# main.net
KiCad netlist of a schematic drawn in EAGLE
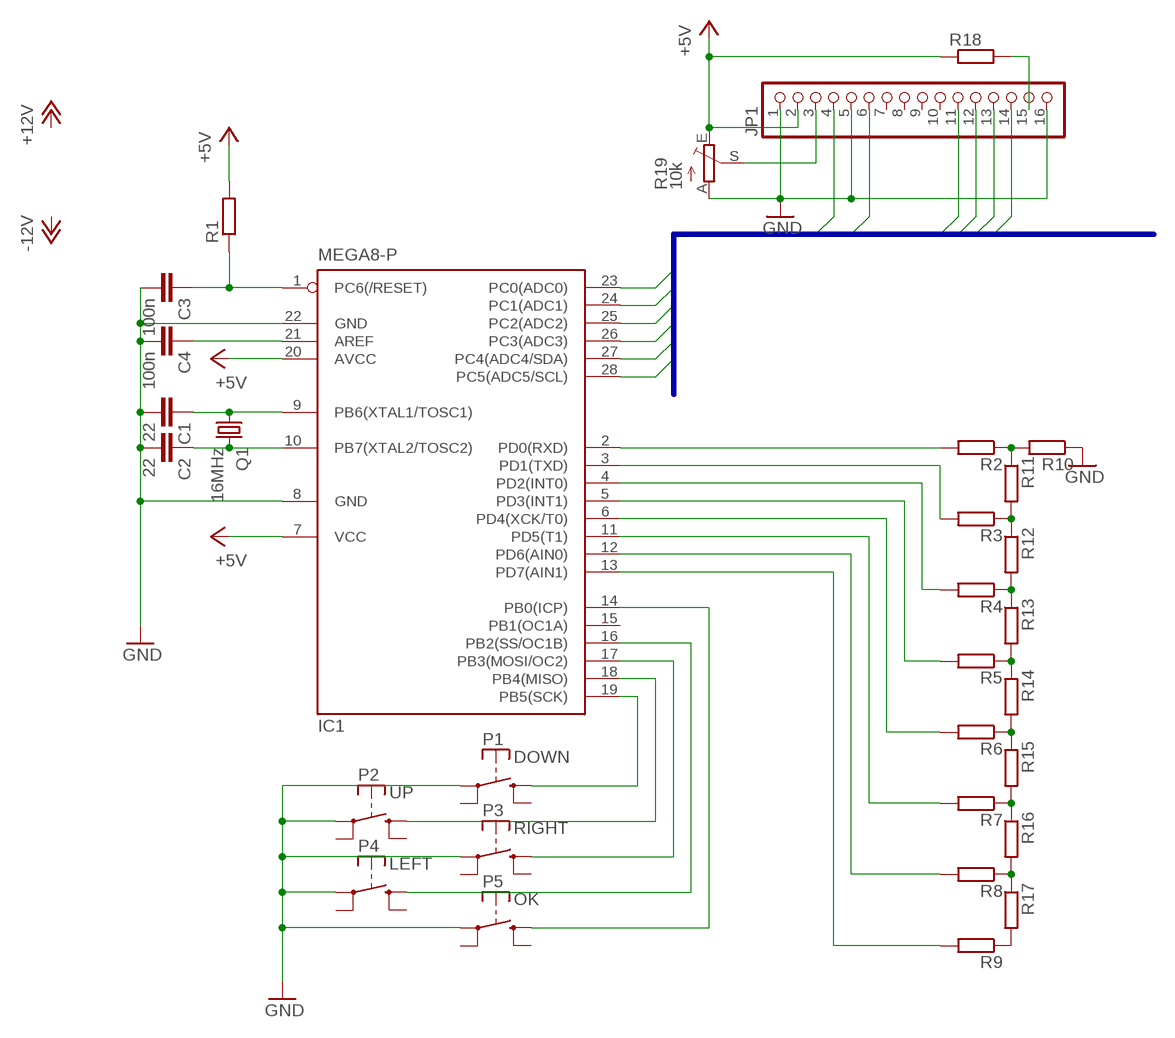
[diagram p0: schematic, sheet 1]

(export (version "E")
  (design (tool "Eeschema 10.0.6"))
  (components
    (comp (ref "C1")
      (value "22")
      (footprint "eagle-import:C0805")
      (libsource (lib "eagle-import") (part "C-EUC0805"))
    )
    (comp (ref "C2")
      (value "22")
      (footprint "eagle-import:C0805")
      (libsource (lib "eagle-import") (part "C-EUC0805"))
    )
    (comp (ref "C3")
      (value "100n")
      (footprint "eagle-import:C0805")
      (libsource (lib "eagle-import") (part "C-EUC0805"))
    )
    (comp (ref "C4")
      (value "100n")
      (footprint "eagle-import:C0805")
      (libsource (lib "eagle-import") (part "C-EUC0805"))
    )
    (comp (ref "IC1")
      (value "MEGA8-P")
      (footprint "eagle-import:DIL28-3")
      (libsource (lib "eagle-import") (part "MEGA8-P"))
    )
    (comp (ref "JP1")
      (value "PINHD-1X16")
      (footprint "eagle-import:1X16")
      (libsource (lib "eagle-import") (part "PINHD-1X16"))
    )
    (comp (ref "P1")
      (value "DOWN")
      (footprint "eagle-import:FSMCD")
      (libsource (lib "eagle-import") (part "FSMCD"))
    )
    (comp (ref "P2")
      (value "UP")
      (footprint "eagle-import:FSMCD")
      (libsource (lib "eagle-import") (part "FSMCD"))
    )
    (comp (ref "P3")
      (value "RIGHT")
      (footprint "eagle-import:FSMCD")
      (libsource (lib "eagle-import") (part "FSMCD"))
    )
    (comp (ref "P4")
      (value "LEFT")
      (footprint "eagle-import:FSMCD")
      (libsource (lib "eagle-import") (part "FSMCD"))
    )
    (comp (ref "P5")
      (value "OK")
      (footprint "eagle-import:FSMCD")
      (libsource (lib "eagle-import") (part "FSMCD"))
    )
    (comp (ref "Q1")
      (value "16MHz")
      (footprint "eagle-import:HC49_S")
      (libsource (lib "eagle-import") (part "CRYSTALHC49S"))
    )
    (comp (ref "R1")
      (value "R-EU_0207/10")
      (footprint "eagle-import:0207_10")
      (libsource (lib "eagle-import") (part "R-EU_0207/10"))
    )
    (comp (ref "R2")
      (value "R-EU_0207/10")
      (footprint "eagle-import:0207_10")
      (libsource (lib "eagle-import") (part "R-EU_0207/10"))
    )
    (comp (ref "R3")
      (value "R-EU_0207/10")
      (footprint "eagle-import:0207_10")
      (libsource (lib "eagle-import") (part "R-EU_0207/10"))
    )
    (comp (ref "R4")
      (value "R-EU_0207/10")
      (footprint "eagle-import:0207_10")
      (libsource (lib "eagle-import") (part "R-EU_0207/10"))
    )
    (comp (ref "R5")
      (value "R-EU_0207/10")
      (footprint "eagle-import:0207_10")
      (libsource (lib "eagle-import") (part "R-EU_0207/10"))
    )
    (comp (ref "R6")
      (value "R-EU_0207/10")
      (footprint "eagle-import:0207_10")
      (libsource (lib "eagle-import") (part "R-EU_0207/10"))
    )
    (comp (ref "R7")
      (value "R-EU_0207/10")
      (footprint "eagle-import:0207_10")
      (libsource (lib "eagle-import") (part "R-EU_0207/10"))
    )
    (comp (ref "R8")
      (value "R-EU_0207/10")
      (footprint "eagle-import:0207_10")
      (libsource (lib "eagle-import") (part "R-EU_0207/10"))
    )
    (comp (ref "R9")
      (value "R-EU_0207/10")
      (footprint "eagle-import:0207_10")
      (libsource (lib "eagle-import") (part "R-EU_0207/10"))
    )
    (comp (ref "R10")
      (value "R-EU_0207/10")
      (footprint "eagle-import:0207_10")
      (libsource (lib "eagle-import") (part "R-EU_0207/10"))
    )
    (comp (ref "R11")
      (value "R-EU_0207/10")
      (footprint "eagle-import:0207_10")
      (libsource (lib "eagle-import") (part "R-EU_0207/10"))
    )
    (comp (ref "R12")
      (value "R-EU_0207/10")
      (footprint "eagle-import:0207_10")
      (libsource (lib "eagle-import") (part "R-EU_0207/10"))
    )
    (comp (ref "R13")
      (value "R-EU_0207/10")
      (footprint "eagle-import:0207_10")
      (libsource (lib "eagle-import") (part "R-EU_0207/10"))
    )
    (comp (ref "R14")
      (value "R-EU_0207/10")
      (footprint "eagle-import:0207_10")
      (libsource (lib "eagle-import") (part "R-EU_0207/10"))
    )
    (comp (ref "R15")
      (value "R-EU_0207/10")
      (footprint "eagle-import:0207_10")
      (libsource (lib "eagle-import") (part "R-EU_0207/10"))
    )
    (comp (ref "R16")
      (value "R-EU_0207/10")
      (footprint "eagle-import:0207_10")
      (libsource (lib "eagle-import") (part "R-EU_0207/10"))
    )
    (comp (ref "R17")
      (value "R-EU_0207/10")
      (footprint "eagle-import:0207_10")
      (libsource (lib "eagle-import") (part "R-EU_0207/10"))
    )
    (comp (ref "R18")
      (value "R-EU_0207/10")
      (footprint "eagle-import:0207_10")
      (libsource (lib "eagle-import") (part "R-EU_0207/10"))
    )
    (comp (ref "R19")
      (value "10k")
      (footprint "eagle-import:CA6V")
      (libsource (lib "eagle-import") (part "TRIM_EU-CA6V"))
    )
  )
  (nets
    (net (code "1") (name "+5V") (class "Default")
      (node (ref "IC1") (pin "20") (pinfunction "AVCC_20") (pintype "power_in"))
      (node (ref "IC1") (pin "7") (pinfunction "VCC_7") (pintype "power_in"))
      (node (ref "JP1") (pin "2") (pinfunction "2_2") (pintype "passive"))
      (node (ref "R1") (pin "2") (pinfunction "2_2") (pintype "passive"))
      (node (ref "R18") (pin "1") (pinfunction "1_1") (pintype "passive"))
      (node (ref "R19") (pin "E") (pinfunction "E_E") (pintype "passive"))
    )
    (net (code "4") (name "/LCD_D4") (class "Default")
      (node (ref "IC1") (pin "23") (pinfunction "PC0(ADC0)_23") (pintype "bidirectional"))
      (node (ref "JP1") (pin "11") (pinfunction "11_11") (pintype "passive"))
    )
    (net (code "5") (name "/LCD_D5") (class "Default")
      (node (ref "IC1") (pin "24") (pinfunction "PC1(ADC1)_24") (pintype "bidirectional"))
      (node (ref "JP1") (pin "12") (pinfunction "12_12") (pintype "passive"))
    )
    (net (code "6") (name "/LCD_D6") (class "Default")
      (node (ref "IC1") (pin "25") (pinfunction "PC2(ADC2)_25") (pintype "bidirectional"))
      (node (ref "JP1") (pin "13") (pinfunction "13_13") (pintype "passive"))
    )
    (net (code "7") (name "/LCD_D7") (class "Default")
      (node (ref "IC1") (pin "26") (pinfunction "PC3(ADC3)_26") (pintype "bidirectional"))
      (node (ref "JP1") (pin "14") (pinfunction "14_14") (pintype "passive"))
    )
    (net (code "8") (name "/LCD_E") (class "Default")
      (node (ref "IC1") (pin "28") (pinfunction "PC5(ADC5/SCL)_28") (pintype "bidirectional"))
      (node (ref "JP1") (pin "6") (pinfunction "6_6") (pintype "passive"))
    )
    (net (code "9") (name "/LCD_RS") (class "Default")
      (node (ref "IC1") (pin "27") (pinfunction "PC4(ADC4/SDA)_27") (pintype "bidirectional"))
      (node (ref "JP1") (pin "4") (pinfunction "4_4") (pintype "passive"))
    )
    (net (code "10") (name "GND") (class "Default")
      (node (ref "C1") (pin "2") (pinfunction "2_2") (pintype "passive"))
      (node (ref "C2") (pin "2") (pinfunction "2_2") (pintype "passive"))
      (node (ref "C3") (pin "2") (pinfunction "2_2") (pintype "passive"))
      (node (ref "C4") (pin "2") (pinfunction "2_2") (pintype "passive"))
      (node (ref "IC1") (pin "22") (pinfunction "GND_22") (pintype "power_in"))
      (node (ref "IC1") (pin "8") (pinfunction "GND_8") (pintype "power_in"))
      (node (ref "JP1") (pin "1") (pinfunction "1_1") (pintype "passive"))
      (node (ref "JP1") (pin "16") (pinfunction "16_16") (pintype "passive"))
      (node (ref "JP1") (pin "5") (pinfunction "5_5") (pintype "passive"))
      (node (ref "P1") (pin "P$1") (pinfunction "P_P$1") (pintype "passive"))
      (node (ref "P2") (pin "P$1") (pinfunction "P_P$1") (pintype "passive"))
      (node (ref "P3") (pin "P$1") (pinfunction "P_P$1") (pintype "passive"))
      (node (ref "P4") (pin "P$1") (pinfunction "P_P$1") (pintype "passive"))
      (node (ref "P5") (pin "P$1") (pinfunction "P_P$1") (pintype "passive"))
      (node (ref "R10") (pin "1") (pinfunction "1_1") (pintype "passive"))
      (node (ref "R19") (pin "A") (pinfunction "A_A") (pintype "passive"))
    )
    (net (code "11") (name "Net-(IC1-AREF)") (class "Default")
      (node (ref "C4") (pin "1") (pinfunction "1_1") (pintype "passive"))
      (node (ref "IC1") (pin "21") (pinfunction "AREF_21") (pintype "passive"))
    )
    (net (code "12") (name "Net-(IC1-PB0(ICP))") (class "Default")
      (node (ref "IC1") (pin "14") (pinfunction "PB0(ICP)_14") (pintype "bidirectional"))
      (node (ref "P5") (pin "P$3") (pinfunction "S_P$3") (pintype "passive"))
    )
    (net (code "13") (name "Net-(IC1-PB2(SS{slash}OC1B))") (class "Default")
      (node (ref "IC1") (pin "16") (pinfunction "PB2(SS/OC1B)_16") (pintype "bidirectional"))
      (node (ref "P4") (pin "P$3") (pinfunction "S_P$3") (pintype "passive"))
    )
    (net (code "14") (name "Net-(IC1-PB3(MOSI{slash}OC2))") (class "Default")
      (node (ref "IC1") (pin "17") (pinfunction "PB3(MOSI/OC2)_17") (pintype "bidirectional"))
      (node (ref "P3") (pin "P$3") (pinfunction "S_P$3") (pintype "passive"))
    )
    (net (code "15") (name "Net-(IC1-PB4(MISO))") (class "Default")
      (node (ref "IC1") (pin "18") (pinfunction "PB4(MISO)_18") (pintype "bidirectional"))
      (node (ref "P2") (pin "P$3") (pinfunction "S_P$3") (pintype "passive"))
    )
    (net (code "16") (name "Net-(IC1-PB5(SCK))") (class "Default")
      (node (ref "IC1") (pin "19") (pinfunction "PB5(SCK)_19") (pintype "bidirectional"))
      (node (ref "P1") (pin "P$3") (pinfunction "S_P$3") (pintype "passive"))
    )
    (net (code "17") (name "Net-(IC1-PB6(XTAL1{slash}TOSC1))") (class "Default")
      (node (ref "C1") (pin "1") (pinfunction "1_1") (pintype "passive"))
      (node (ref "IC1") (pin "9") (pinfunction "PB6(XTAL1/TOSC1)_9") (pintype "bidirectional"))
      (node (ref "Q1") (pin "1") (pinfunction "1_1") (pintype "passive"))
    )
    (net (code "18") (name "Net-(IC1-PB7(XTAL2{slash}TOSC2))") (class "Default")
      (node (ref "C2") (pin "1") (pinfunction "1_1") (pintype "passive"))
      (node (ref "IC1") (pin "10") (pinfunction "PB7(XTAL2/TOSC2)_10") (pintype "bidirectional"))
      (node (ref "Q1") (pin "2") (pinfunction "2_2") (pintype "passive"))
    )
    (net (code "19") (name "Net-(IC1-PC6({slash}RESET))") (class "Default")
      (node (ref "C3") (pin "1") (pinfunction "1_1") (pintype "passive"))
      (node (ref "IC1") (pin "1") (pinfunction "PC6(/RESET)_1") (pintype "bidirectional"))
      (node (ref "R1") (pin "1") (pinfunction "1_1") (pintype "passive"))
    )
    (net (code "20") (name "Net-(IC1-PD0(RXD))") (class "Default")
      (node (ref "IC1") (pin "2") (pinfunction "PD0(RXD)_2") (pintype "bidirectional"))
      (node (ref "R2") (pin "2") (pinfunction "2_2") (pintype "passive"))
    )
    (net (code "21") (name "Net-(IC1-PD1(TXD))") (class "Default")
      (node (ref "IC1") (pin "3") (pinfunction "PD1(TXD)_3") (pintype "bidirectional"))
      (node (ref "R3") (pin "2") (pinfunction "2_2") (pintype "passive"))
    )
    (net (code "22") (name "Net-(IC1-PD2(INT0))") (class "Default")
      (node (ref "IC1") (pin "4") (pinfunction "PD2(INT0)_4") (pintype "bidirectional"))
      (node (ref "R4") (pin "2") (pinfunction "2_2") (pintype "passive"))
    )
    (net (code "23") (name "Net-(IC1-PD3(INT1))") (class "Default")
      (node (ref "IC1") (pin "5") (pinfunction "PD3(INT1)_5") (pintype "bidirectional"))
      (node (ref "R5") (pin "2") (pinfunction "2_2") (pintype "passive"))
    )
    (net (code "24") (name "Net-(IC1-PD4(XCK{slash}T0))") (class "Default")
      (node (ref "IC1") (pin "6") (pinfunction "PD4(XCK/T0)_6") (pintype "bidirectional"))
      (node (ref "R6") (pin "2") (pinfunction "2_2") (pintype "passive"))
    )
    (net (code "25") (name "Net-(IC1-PD5(T1))") (class "Default")
      (node (ref "IC1") (pin "11") (pinfunction "PD5(T1)_11") (pintype "bidirectional"))
      (node (ref "R7") (pin "2") (pinfunction "2_2") (pintype "passive"))
    )
    (net (code "26") (name "Net-(IC1-PD6(AIN0))") (class "Default")
      (node (ref "IC1") (pin "12") (pinfunction "PD6(AIN0)_12") (pintype "bidirectional"))
      (node (ref "R8") (pin "2") (pinfunction "2_2") (pintype "passive"))
    )
    (net (code "27") (name "Net-(IC1-PD7(AIN1))") (class "Default")
      (node (ref "IC1") (pin "13") (pinfunction "PD7(AIN1)_13") (pintype "bidirectional"))
      (node (ref "R9") (pin "2") (pinfunction "2_2") (pintype "passive"))
    )
    (net (code "28") (name "Net-(JP1-Pad3)") (class "Default")
      (node (ref "JP1") (pin "3") (pinfunction "3_3") (pintype "passive"))
      (node (ref "R19") (pin "S") (pinfunction "S_S") (pintype "passive"))
    )
    (net (code "29") (name "Net-(JP1-Pad15)") (class "Default")
      (node (ref "JP1") (pin "15") (pinfunction "15_15") (pintype "passive"))
      (node (ref "R18") (pin "2") (pinfunction "2_2") (pintype "passive"))
    )
    (net (code "30") (name "Net-(R10-Pad2)") (class "Default")
      (node (ref "R10") (pin "2") (pinfunction "2_2") (pintype "passive"))
      (node (ref "R11") (pin "1") (pinfunction "1_1") (pintype "passive"))
      (node (ref "R2") (pin "1") (pinfunction "1_1") (pintype "passive"))
    )
    (net (code "31") (name "Net-(R11-Pad2)") (class "Default")
      (node (ref "R11") (pin "2") (pinfunction "2_2") (pintype "passive"))
      (node (ref "R12") (pin "1") (pinfunction "1_1") (pintype "passive"))
      (node (ref "R3") (pin "1") (pinfunction "1_1") (pintype "passive"))
    )
    (net (code "32") (name "Net-(R12-Pad2)") (class "Default")
      (node (ref "R12") (pin "2") (pinfunction "2_2") (pintype "passive"))
      (node (ref "R13") (pin "1") (pinfunction "1_1") (pintype "passive"))
      (node (ref "R4") (pin "1") (pinfunction "1_1") (pintype "passive"))
    )
    (net (code "33") (name "Net-(R13-Pad2)") (class "Default")
      (node (ref "R13") (pin "2") (pinfunction "2_2") (pintype "passive"))
      (node (ref "R14") (pin "1") (pinfunction "1_1") (pintype "passive"))
      (node (ref "R5") (pin "1") (pinfunction "1_1") (pintype "passive"))
    )
    (net (code "34") (name "Net-(R14-Pad2)") (class "Default")
      (node (ref "R14") (pin "2") (pinfunction "2_2") (pintype "passive"))
      (node (ref "R15") (pin "1") (pinfunction "1_1") (pintype "passive"))
      (node (ref "R6") (pin "1") (pinfunction "1_1") (pintype "passive"))
    )
    (net (code "35") (name "Net-(R15-Pad2)") (class "Default")
      (node (ref "R15") (pin "2") (pinfunction "2_2") (pintype "passive"))
      (node (ref "R16") (pin "1") (pinfunction "1_1") (pintype "passive"))
      (node (ref "R7") (pin "1") (pinfunction "1_1") (pintype "passive"))
    )
    (net (code "36") (name "Net-(R16-Pad2)") (class "Default")
      (node (ref "R16") (pin "2") (pinfunction "2_2") (pintype "passive"))
      (node (ref "R17") (pin "1") (pinfunction "1_1") (pintype "passive"))
      (node (ref "R8") (pin "1") (pinfunction "1_1") (pintype "passive"))
    )
    (net (code "37") (name "Net-(R17-Pad2)") (class "Default")
      (node (ref "R17") (pin "2") (pinfunction "2_2") (pintype "passive"))
      (node (ref "R9") (pin "1") (pinfunction "1_1") (pintype "passive"))
    )
    (net (code "38") (name "unconnected-(IC1-PB1(OC1A)-Pad15)") (class "Default")
      (node (ref "IC1") (pin "15") (pinfunction "PB1(OC1A)_15") (pintype "bidirectional"))
    )
    (net (code "39") (name "unconnected-(JP1-Pad7)") (class "Default")
      (node (ref "JP1") (pin "7") (pinfunction "7_7") (pintype "passive"))
    )
    (net (code "40") (name "unconnected-(JP1-Pad8)") (class "Default")
      (node (ref "JP1") (pin "8") (pinfunction "8_8") (pintype "passive"))
    )
    (net (code "41") (name "unconnected-(JP1-Pad9)") (class "Default")
      (node (ref "JP1") (pin "9") (pinfunction "9_9") (pintype "passive"))
    )
    (net (code "42") (name "unconnected-(JP1-Pad10)") (class "Default")
      (node (ref "JP1") (pin "10") (pinfunction "10_10") (pintype "passive"))
    )
    (net (code "43") (name "unconnected-(P1-P-PadP$2)") (class "Default")
      (node (ref "P1") (pin "P$2") (pinfunction "P_P$2") (pintype "passive"))
    )
    (net (code "44") (name "unconnected-(P1-S-PadP$4)") (class "Default")
      (node (ref "P1") (pin "P$4") (pinfunction "S_P$4") (pintype "passive"))
    )
    (net (code "45") (name "unconnected-(P2-P-PadP$2)") (class "Default")
      (node (ref "P2") (pin "P$2") (pinfunction "P_P$2") (pintype "passive"))
    )
    (net (code "46") (name "unconnected-(P2-S-PadP$4)") (class "Default")
      (node (ref "P2") (pin "P$4") (pinfunction "S_P$4") (pintype "passive"))
    )
    (net (code "47") (name "unconnected-(P3-P-PadP$2)") (class "Default")
      (node (ref "P3") (pin "P$2") (pinfunction "P_P$2") (pintype "passive"))
    )
    (net (code "48") (name "unconnected-(P3-S-PadP$4)") (class "Default")
      (node (ref "P3") (pin "P$4") (pinfunction "S_P$4") (pintype "passive"))
    )
    (net (code "49") (name "unconnected-(P4-P-PadP$2)") (class "Default")
      (node (ref "P4") (pin "P$2") (pinfunction "P_P$2") (pintype "passive"))
    )
    (net (code "50") (name "unconnected-(P4-S-PadP$4)") (class "Default")
      (node (ref "P4") (pin "P$4") (pinfunction "S_P$4") (pintype "passive"))
    )
    (net (code "51") (name "unconnected-(P5-P-PadP$2)") (class "Default")
      (node (ref "P5") (pin "P$2") (pinfunction "P_P$2") (pintype "passive"))
    )
    (net (code "52") (name "unconnected-(P5-S-PadP$4)") (class "Default")
      (node (ref "P5") (pin "P$4") (pinfunction "S_P$4") (pintype "passive"))
    )
  )
)
